# obc-v2_CM4-IRQ-CTRL.net
KiCad netlist of a schematic drawn in Altium Designer
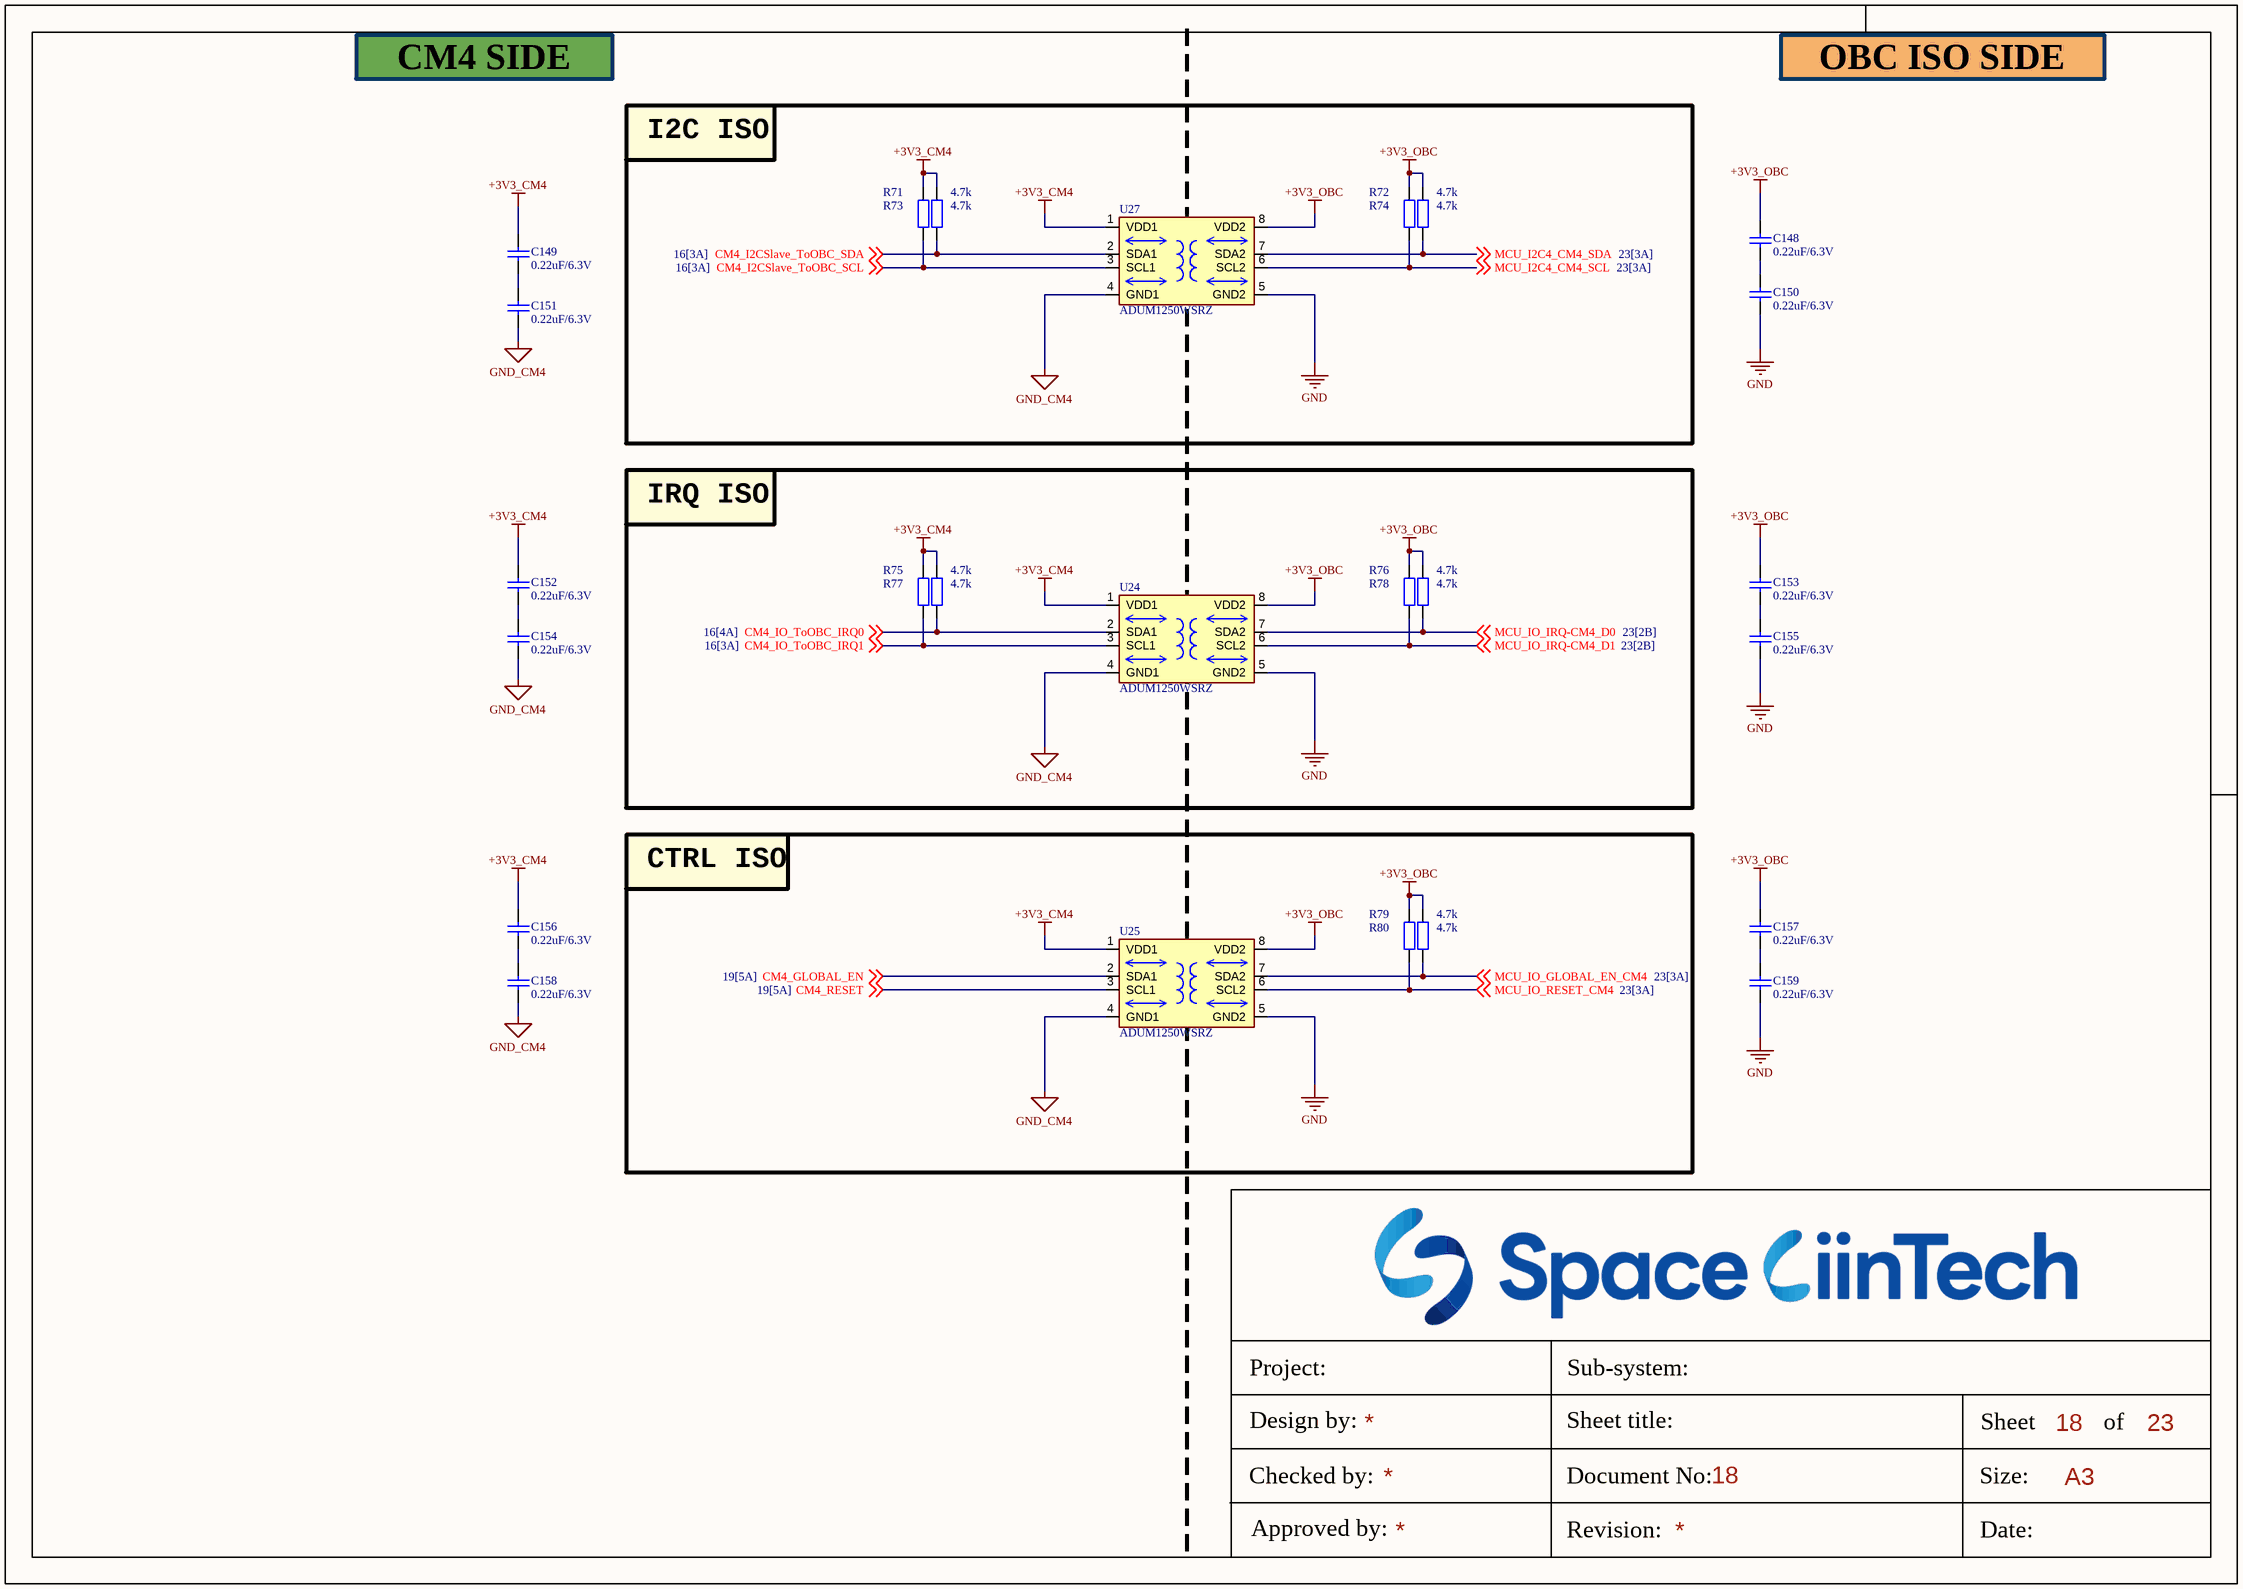
[diagram p0: obc-v2_CM4-IRQ-CTRL.SchDoc]

(export (version "E")
  (design (tool "Eeschema 10.0.6"))
  (components
    (comp (ref "C148")
      (value "0.22uF/6.3V")
      (footprint "CAP_C_1005X60")
      (description "CAPC")
      (libsource (lib "Altium_Lib_by_KhueNguyenCreator") (part "Tu 0402 33nF 10V"))
    )
    (comp (ref "C149")
      (value "0.22uF/6.3V")
      (footprint "CAP_C_1005X60")
      (description "CAPC")
      (libsource (lib "Altium_Lib_by_KhueNguyenCreator") (part "Tu 0402 33nF 10V"))
    )
    (comp (ref "C150")
      (value "0.22uF/6.3V")
      (footprint "CAP_C_1005X60")
      (description "CAPC")
      (libsource (lib "Altium_Lib_by_KhueNguyenCreator") (part "Tu 0402 33nF 10V"))
    )
    (comp (ref "C151")
      (value "0.22uF/6.3V")
      (footprint "CAP_C_1005X60")
      (description "CAPC")
      (libsource (lib "Altium_Lib_by_KhueNguyenCreator") (part "Tu 0402 33nF 10V"))
    )
    (comp (ref "C152")
      (value "0.22uF/6.3V")
      (footprint "CAP_C_1005X60")
      (description "CAPC")
      (libsource (lib "Altium_Lib_by_KhueNguyenCreator") (part "Tu 0402 33nF 10V"))
    )
    (comp (ref "C153")
      (value "0.22uF/6.3V")
      (footprint "CAP_C_1005X60")
      (description "CAPC")
      (libsource (lib "Altium_Lib_by_KhueNguyenCreator") (part "Tu 0402 33nF 10V"))
    )
    (comp (ref "C154")
      (value "0.22uF/6.3V")
      (footprint "CAP_C_1005X60")
      (description "CAPC")
      (libsource (lib "Altium_Lib_by_KhueNguyenCreator") (part "Tu 0402 33nF 10V"))
    )
    (comp (ref "C155")
      (value "0.22uF/6.3V")
      (footprint "CAP_C_1005X60")
      (description "CAPC")
      (libsource (lib "Altium_Lib_by_KhueNguyenCreator") (part "Tu 0402 33nF 10V"))
    )
    (comp (ref "C156")
      (value "0.22uF/6.3V")
      (footprint "CAP_C_1005X60")
      (description "CAPC")
      (libsource (lib "Altium_Lib_by_KhueNguyenCreator") (part "Tu 0402 33nF 10V"))
    )
    (comp (ref "C157")
      (value "0.22uF/6.3V")
      (footprint "CAP_C_1005X60")
      (description "CAPC")
      (libsource (lib "Altium_Lib_by_KhueNguyenCreator") (part "Tu 0402 33nF 10V"))
    )
    (comp (ref "C158")
      (value "0.22uF/6.3V")
      (footprint "CAP_C_1005X60")
      (description "CAPC")
      (libsource (lib "Altium_Lib_by_KhueNguyenCreator") (part "Tu 0402 33nF 10V"))
    )
    (comp (ref "C159")
      (value "0.22uF/6.3V")
      (footprint "CAP_C_1005X60")
      (description "CAPC")
      (libsource (lib "Altium_Lib_by_KhueNguyenCreator") (part "Tu 0402 33nF 10V"))
    )
    (comp (ref "R71")
      (value "4.7k")
      (footprint "RES_C_1608X60")
      (description "RES")
      (libsource (lib "Altium_Lib_by_KhueNguyenCreator") (part "Tro 0603 1% 10k"))
    )
    (comp (ref "R72")
      (value "4.7k")
      (footprint "RES_C_1608X60")
      (description "RES")
      (libsource (lib "Altium_Lib_by_KhueNguyenCreator") (part "Tro 0603 1% 10k"))
    )
    (comp (ref "R73")
      (value "4.7k")
      (footprint "RES_C_1608X60")
      (description "RES")
      (libsource (lib "Altium_Lib_by_KhueNguyenCreator") (part "Tro 0603 1% 10k"))
    )
    (comp (ref "R74")
      (value "4.7k")
      (footprint "RES_C_1608X60")
      (description "RES")
      (libsource (lib "Altium_Lib_by_KhueNguyenCreator") (part "Tro 0603 1% 10k"))
    )
    (comp (ref "R75")
      (value "4.7k")
      (footprint "RES_C_1608X60")
      (description "RES")
      (libsource (lib "Altium_Lib_by_KhueNguyenCreator") (part "Tro 0603 1% 10k"))
    )
    (comp (ref "R76")
      (value "4.7k")
      (footprint "RES_C_1608X60")
      (description "RES")
      (libsource (lib "Altium_Lib_by_KhueNguyenCreator") (part "Tro 0603 1% 10k"))
    )
    (comp (ref "R77")
      (value "4.7k")
      (footprint "RES_C_1608X60")
      (description "RES")
      (libsource (lib "Altium_Lib_by_KhueNguyenCreator") (part "Tro 0603 1% 10k"))
    )
    (comp (ref "R78")
      (value "4.7k")
      (footprint "RES_C_1608X60")
      (description "RES")
      (libsource (lib "Altium_Lib_by_KhueNguyenCreator") (part "Tro 0603 1% 10k"))
    )
    (comp (ref "R79")
      (value "4.7k")
      (footprint "RES_C_1608X60")
      (description "RES")
      (libsource (lib "Altium_Lib_by_KhueNguyenCreator") (part "Tro 0603 1% 10k"))
    )
    (comp (ref "R80")
      (value "4.7k")
      (footprint "RES_C_1608X60")
      (description "RES")
      (libsource (lib "Altium_Lib_by_KhueNguyenCreator") (part "Tro 0603 1% 10k"))
    )
    (comp (ref "U24")
      (value "ADUM1250WSRZ")
      (footprint "SOIC127P602X173-8N")
      (description "I虏C Digital Isolator 2500Vrms 2 Channel 1Mbps 25kV/碌s CMTI 8-SOIC (0.154\", 3.90mm Width)")
      (fields (field (name "MF") "Analog Devices") (field (name "MP") "ADUM1250"))
      (libsource (lib "ADUM1250") (part "ADUM1250"))
    )
    (comp (ref "U25")
      (value "ADUM1250WSRZ")
      (footprint "SOIC127P602X173-8N")
      (description "I虏C Digital Isolator 2500Vrms 2 Channel 1Mbps 25kV/碌s CMTI 8-SOIC (0.154\", 3.90mm Width)")
      (fields (field (name "MF") "Analog Devices") (field (name "MP") "ADUM1250"))
      (libsource (lib "ADUM1250") (part "ADUM1250"))
    )
    (comp (ref "U27")
      (value "ADUM1250WSRZ")
      (footprint "SOIC127P602X173-8N")
      (description "I虏C Digital Isolator 2500Vrms 2 Channel 1Mbps 25kV/碌s CMTI 8-SOIC (0.154\", 3.90mm Width)")
      (fields (field (name "MF") "Analog Devices") (field (name "MP") "ADUM1250"))
      (libsource (lib "ADUM1250") (part "ADUM1250"))
    )
  )
  (nets
    (net (code "1") (name "+3V3_CM4") (class "Default")
      (node (ref "C149") (pin "1") (pinfunction "1_1") (pintype "passive"))
      (node (ref "C152") (pin "1") (pinfunction "1_1") (pintype "passive"))
      (node (ref "C156") (pin "1") (pinfunction "1_1") (pintype "passive"))
      (node (ref "R71") (pin "2") (pinfunction "2_2") (pintype "passive"))
      (node (ref "R73") (pin "2") (pinfunction "2_2") (pintype "passive"))
      (node (ref "R75") (pin "2") (pinfunction "2_2") (pintype "passive"))
      (node (ref "R77") (pin "2") (pinfunction "2_2") (pintype "passive"))
      (node (ref "U24") (pin "1") (pinfunction "VDD1_1") (pintype "power_in"))
      (node (ref "U25") (pin "1") (pinfunction "VDD1_1") (pintype "power_in"))
      (node (ref "U27") (pin "1") (pinfunction "VDD1_1") (pintype "power_in"))
    )
    (net (code "2") (name "+3V3_OBC") (class "Default")
      (node (ref "C148") (pin "1") (pinfunction "1_1") (pintype "passive"))
      (node (ref "C153") (pin "1") (pinfunction "1_1") (pintype "passive"))
      (node (ref "C157") (pin "1") (pinfunction "1_1") (pintype "passive"))
      (node (ref "R72") (pin "2") (pinfunction "2_2") (pintype "passive"))
      (node (ref "R74") (pin "2") (pinfunction "2_2") (pintype "passive"))
      (node (ref "R76") (pin "2") (pinfunction "2_2") (pintype "passive"))
      (node (ref "R78") (pin "2") (pinfunction "2_2") (pintype "passive"))
      (node (ref "R79") (pin "2") (pinfunction "2_2") (pintype "passive"))
      (node (ref "R80") (pin "2") (pinfunction "2_2") (pintype "passive"))
      (node (ref "U24") (pin "8") (pinfunction "VDD2_8") (pintype "power_in"))
      (node (ref "U25") (pin "8") (pinfunction "VDD2_8") (pintype "power_in"))
      (node (ref "U27") (pin "8") (pinfunction "VDD2_8") (pintype "power_in"))
    )
    (net (code "3") (name "CM4_GLOBAL_EN") (class "Default")
      (node (ref "U25") (pin "2") (pinfunction "SDA1_2") (pintype "bidirectional"))
    )
    (net (code "4") (name "CM4_I2CSlave_ToOBC_SCL") (class "Default")
      (node (ref "R71") (pin "1") (pinfunction "1_1") (pintype "passive"))
      (node (ref "U27") (pin "3") (pinfunction "SCL1_3") (pintype "bidirectional"))
    )
    (net (code "5") (name "CM4_I2CSlave_ToOBC_SDA") (class "Default")
      (node (ref "R73") (pin "1") (pinfunction "1_1") (pintype "passive"))
      (node (ref "U27") (pin "2") (pinfunction "SDA1_2") (pintype "bidirectional"))
    )
    (net (code "6") (name "CM4_IO_ToOBC_IRQ0") (class "Default")
      (node (ref "R77") (pin "1") (pinfunction "1_1") (pintype "passive"))
      (node (ref "U24") (pin "2") (pinfunction "SDA1_2") (pintype "bidirectional"))
    )
    (net (code "7") (name "CM4_IO_ToOBC_IRQ1") (class "Default")
      (node (ref "R75") (pin "1") (pinfunction "1_1") (pintype "passive"))
      (node (ref "U24") (pin "3") (pinfunction "SCL1_3") (pintype "bidirectional"))
    )
    (net (code "8") (name "CM4_RESET") (class "Default")
      (node (ref "U25") (pin "3") (pinfunction "SCL1_3") (pintype "bidirectional"))
    )
    (net (code "9") (name "GND") (class "Default")
      (node (ref "C150") (pin "2") (pinfunction "2_2") (pintype "passive"))
      (node (ref "C155") (pin "2") (pinfunction "2_2") (pintype "passive"))
      (node (ref "C159") (pin "2") (pinfunction "2_2") (pintype "passive"))
      (node (ref "U24") (pin "5") (pinfunction "GND2_5") (pintype "power_in"))
      (node (ref "U25") (pin "5") (pinfunction "GND2_5") (pintype "power_in"))
      (node (ref "U27") (pin "5") (pinfunction "GND2_5") (pintype "power_in"))
    )
    (net (code "10") (name "GND_CM4") (class "Default")
      (node (ref "C151") (pin "2") (pinfunction "2_2") (pintype "passive"))
      (node (ref "C154") (pin "2") (pinfunction "2_2") (pintype "passive"))
      (node (ref "C158") (pin "2") (pinfunction "2_2") (pintype "passive"))
      (node (ref "U24") (pin "4") (pinfunction "GND1_4") (pintype "power_in"))
      (node (ref "U25") (pin "4") (pinfunction "GND1_4") (pintype "power_in"))
      (node (ref "U27") (pin "4") (pinfunction "GND1_4") (pintype "power_in"))
    )
    (net (code "11") (name "MCU_I2C4_CM4_SCL") (class "Default")
      (node (ref "R72") (pin "1") (pinfunction "1_1") (pintype "passive"))
      (node (ref "U27") (pin "6") (pinfunction "SCL2_6") (pintype "bidirectional"))
    )
    (net (code "12") (name "MCU_I2C4_CM4_SDA") (class "Default")
      (node (ref "R74") (pin "1") (pinfunction "1_1") (pintype "passive"))
      (node (ref "U27") (pin "7") (pinfunction "SDA2_7") (pintype "bidirectional"))
    )
    (net (code "13") (name "MCU_IO_GLOBAL_EN_CM4") (class "Default")
      (node (ref "R80") (pin "1") (pinfunction "1_1") (pintype "passive"))
      (node (ref "U25") (pin "7") (pinfunction "SDA2_7") (pintype "bidirectional"))
    )
    (net (code "14") (name "MCU_IO_IRQ-CM4_D0") (class "Default")
      (node (ref "R78") (pin "1") (pinfunction "1_1") (pintype "passive"))
      (node (ref "U24") (pin "7") (pinfunction "SDA2_7") (pintype "bidirectional"))
    )
    (net (code "15") (name "MCU_IO_IRQ-CM4_D1") (class "Default")
      (node (ref "R76") (pin "1") (pinfunction "1_1") (pintype "passive"))
      (node (ref "U24") (pin "6") (pinfunction "SCL2_6") (pintype "bidirectional"))
    )
    (net (code "16") (name "MCU_IO_RESET_CM4") (class "Default")
      (node (ref "R79") (pin "1") (pinfunction "1_1") (pintype "passive"))
      (node (ref "U25") (pin "6") (pinfunction "SCL2_6") (pintype "bidirectional"))
    )
    (net (code "17") (name "Net-(C148-Pad2)") (class "Default")
      (node (ref "C148") (pin "2") (pinfunction "2_2") (pintype "passive"))
      (node (ref "C150") (pin "1") (pinfunction "1_1") (pintype "passive"))
    )
    (net (code "18") (name "Net-(C149-Pad2)") (class "Default")
      (node (ref "C149") (pin "2") (pinfunction "2_2") (pintype "passive"))
      (node (ref "C151") (pin "1") (pinfunction "1_1") (pintype "passive"))
    )
    (net (code "19") (name "Net-(C152-Pad2)") (class "Default")
      (node (ref "C152") (pin "2") (pinfunction "2_2") (pintype "passive"))
      (node (ref "C154") (pin "1") (pinfunction "1_1") (pintype "passive"))
    )
    (net (code "20") (name "Net-(C153-Pad2)") (class "Default")
      (node (ref "C153") (pin "2") (pinfunction "2_2") (pintype "passive"))
      (node (ref "C155") (pin "1") (pinfunction "1_1") (pintype "passive"))
    )
    (net (code "21") (name "Net-(C156-Pad2)") (class "Default")
      (node (ref "C156") (pin "2") (pinfunction "2_2") (pintype "passive"))
      (node (ref "C158") (pin "1") (pinfunction "1_1") (pintype "passive"))
    )
    (net (code "22") (name "Net-(C157-Pad2)") (class "Default")
      (node (ref "C157") (pin "2") (pinfunction "2_2") (pintype "passive"))
      (node (ref "C159") (pin "1") (pinfunction "1_1") (pintype "passive"))
    )
  )
)
